# Wio_MB128_Test_rev_A.net
KiCad netlist of a schematic drawn in EAGLE
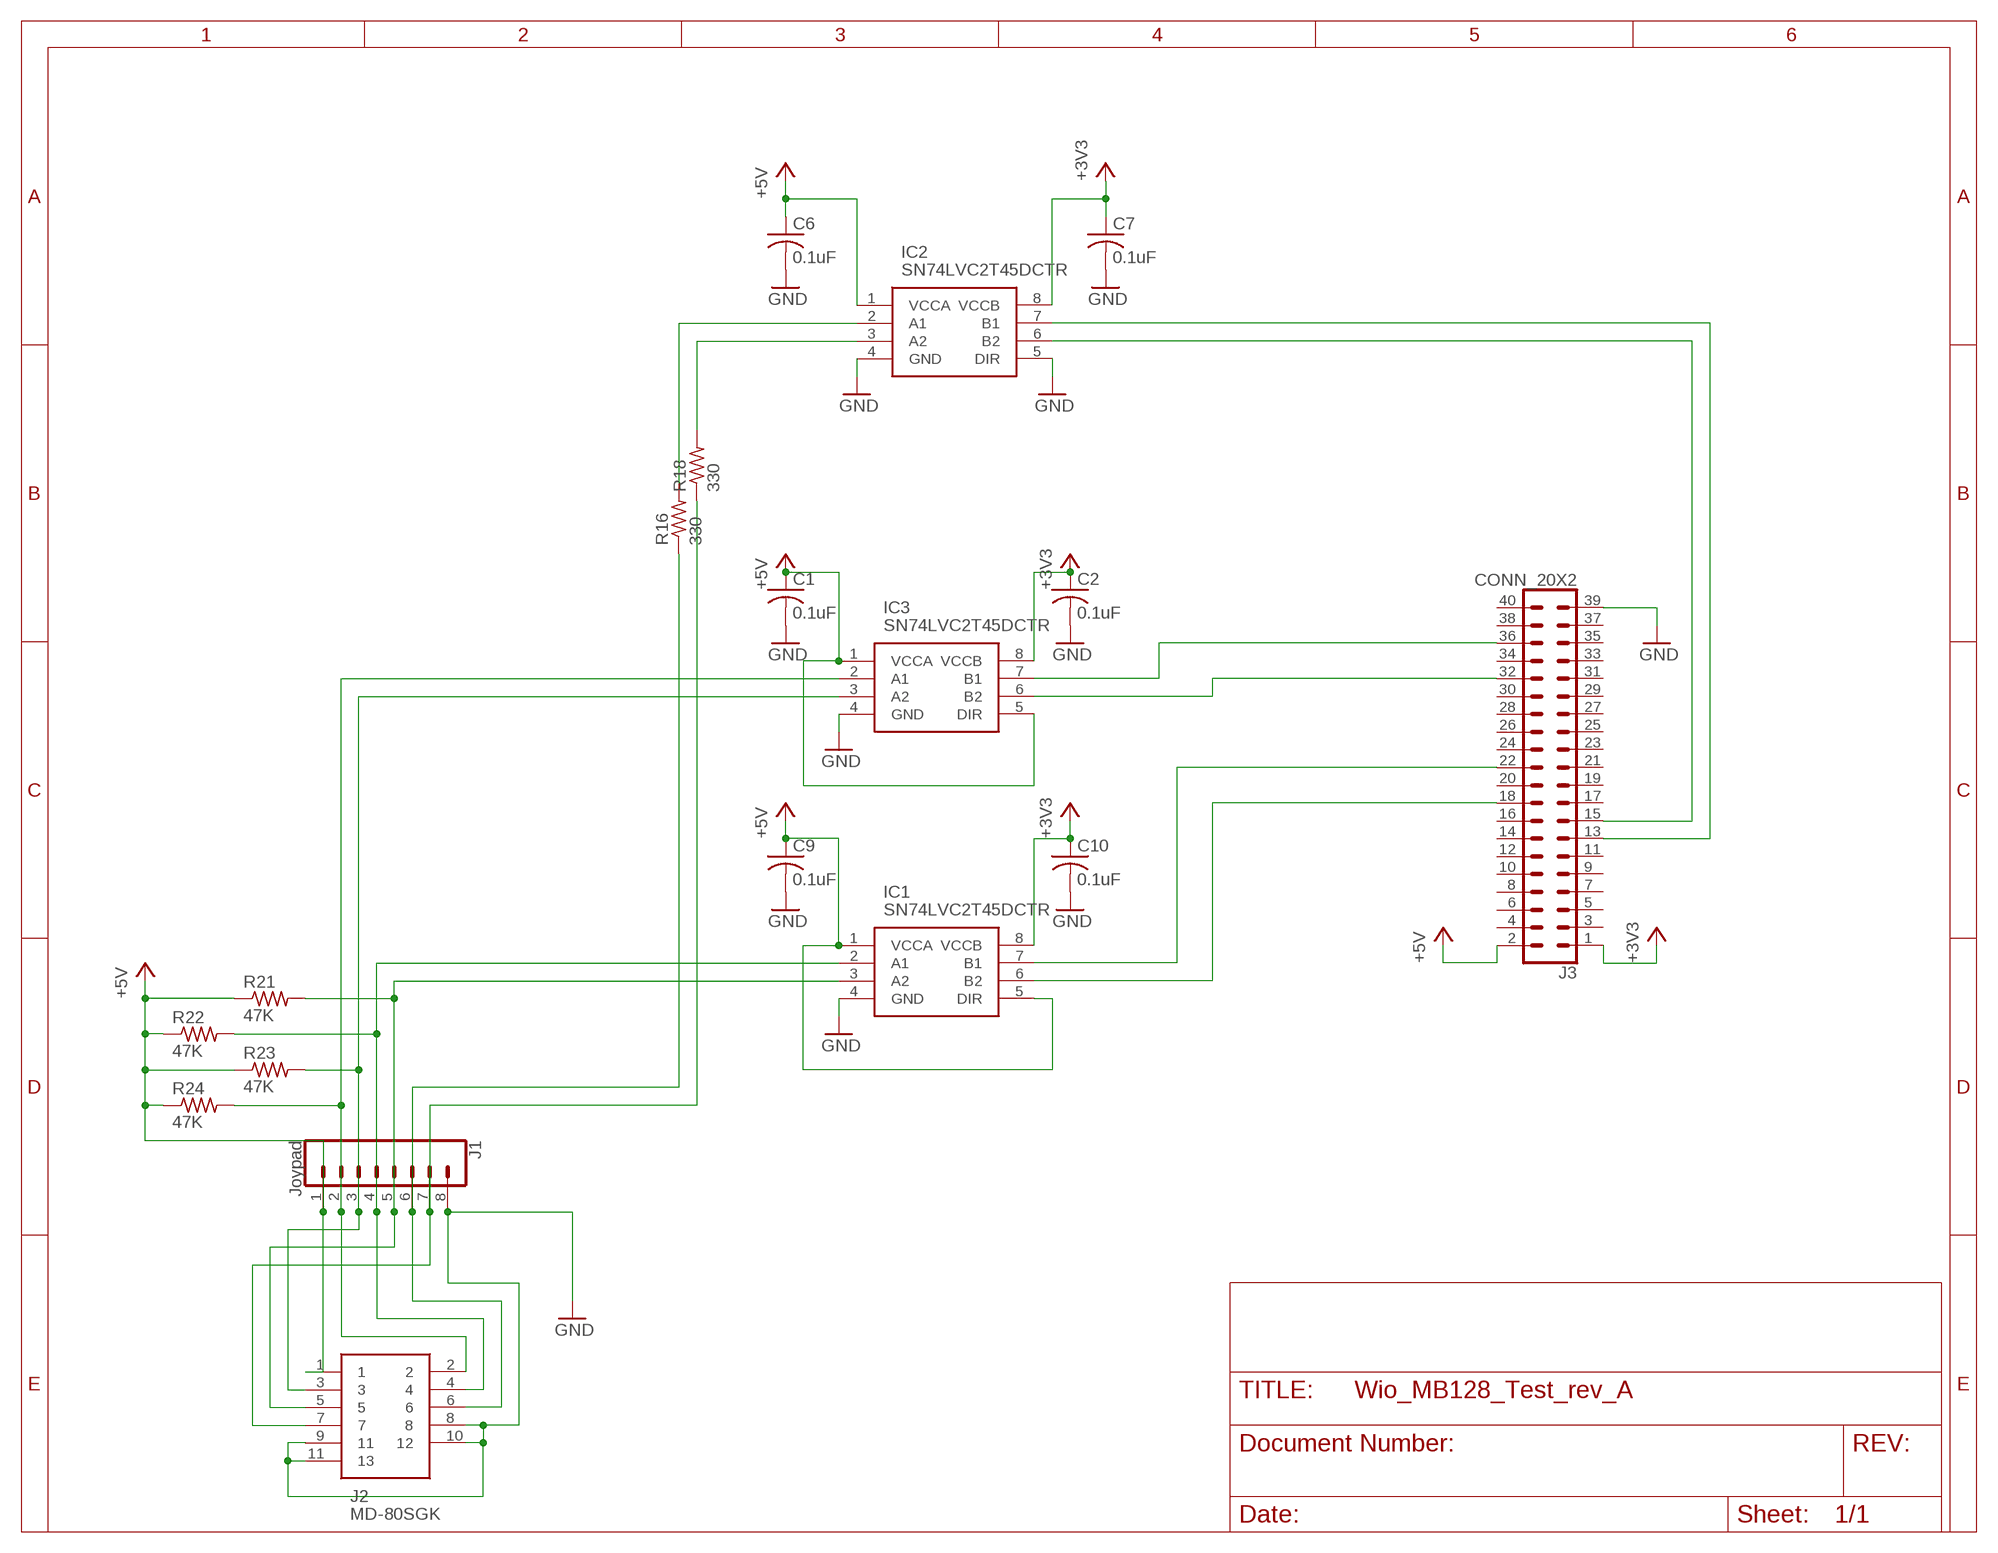
[diagram p0: schematic, sheet 1]

(export (version "E")
  (design (tool "Eeschema 10.0.6"))
  (components
    (comp (ref "C1")
      (value "0.1uF")
      (footprint "eagle-import:C0603")
      (libsource (lib "eagle-import") (part "C-USC0603"))
    )
    (comp (ref "C2")
      (value "0.1uF")
      (footprint "eagle-import:C0603")
      (libsource (lib "eagle-import") (part "C-USC0603"))
    )
    (comp (ref "C6")
      (value "0.1uF")
      (footprint "eagle-import:C0603")
      (libsource (lib "eagle-import") (part "C-USC0603"))
    )
    (comp (ref "C7")
      (value "0.1uF")
      (footprint "eagle-import:C0603")
      (libsource (lib "eagle-import") (part "C-USC0603"))
    )
    (comp (ref "C9")
      (value "0.1uF")
      (footprint "eagle-import:C0603")
      (libsource (lib "eagle-import") (part "C-USC0603"))
    )
    (comp (ref "C10")
      (value "0.1uF")
      (footprint "eagle-import:C0603")
      (libsource (lib "eagle-import") (part "C-USC0603"))
    )
    (comp (ref "IC1")
      (value "SN74LVC2T45DCTR")
      (footprint "eagle-import:SOP65P400X130-8N")
      (fields
        (field (name "MOUSER_PART_NUMBER") "595-SN74LVC2T45DCTR")
        (field (name "RS_PART_NUMBER") "9213022")
      )
      (libsource (lib "eagle-import") (part "SN74LVC2T45DCTR"))
    )
    (comp (ref "IC2")
      (value "SN74LVC2T45DCTR")
      (footprint "eagle-import:SOP65P400X130-8N")
      (fields
        (field (name "MOUSER_PART_NUMBER") "595-SN74LVC2T45DCTR")
        (field (name "RS_PART_NUMBER") "9213022")
      )
      (libsource (lib "eagle-import") (part "SN74LVC2T45DCTR"))
    )
    (comp (ref "IC3")
      (value "SN74LVC2T45DCTR")
      (footprint "eagle-import:SOP65P400X130-8N")
      (fields
        (field (name "MOUSER_PART_NUMBER") "595-SN74LVC2T45DCTR")
        (field (name "RS_PART_NUMBER") "9213022")
      )
      (libsource (lib "eagle-import") (part "SN74LVC2T45DCTR"))
    )
    (comp (ref "J1")
      (value "Joypad")
      (footprint "eagle-import:1X08")
      (libsource (lib "eagle-import") (part "CONN_08{dblquote}"))
    )
    (comp (ref "J2")
      (value "MD-80SGK")
      (footprint "eagle-import:MD80SGK")
      (fields (field (name "MOUSER_PART_NUMBER") "490-MD-80SGK"))
      (libsource (lib "eagle-import") (part "MD-80SGK"))
    )
    (comp (ref "J3")
      (value "CONN_20X2")
      (footprint "eagle-import:2X20")
      (libsource (lib "eagle-import") (part "CONN_20X2"))
    )
    (comp (ref "R16")
      (value "330")
      (footprint "eagle-import:R0603")
      (libsource (lib "eagle-import") (part "R-US_R0603"))
    )
    (comp (ref "R18")
      (value "330")
      (footprint "eagle-import:R0603")
      (libsource (lib "eagle-import") (part "R-US_R0603"))
    )
    (comp (ref "R21")
      (value "47K")
      (footprint "eagle-import:R0603")
      (libsource (lib "eagle-import") (part "R-US_R0603"))
    )
    (comp (ref "R22")
      (value "47K")
      (footprint "eagle-import:R0603")
      (libsource (lib "eagle-import") (part "R-US_R0603"))
    )
    (comp (ref "R23")
      (value "47K")
      (footprint "eagle-import:R0603")
      (libsource (lib "eagle-import") (part "R-US_R0603"))
    )
    (comp (ref "R24")
      (value "47K")
      (footprint "eagle-import:R0603")
      (libsource (lib "eagle-import") (part "R-US_R0603"))
    )
  )
  (nets
    (net (code "1") (name "+3V3") (class "Default")
      (node (ref "C10") (pin "1") (pinfunction "1_1") (pintype "passive"))
      (node (ref "C2") (pin "1") (pinfunction "1_1") (pintype "passive"))
      (node (ref "C7") (pin "1") (pinfunction "1_1") (pintype "passive"))
      (node (ref "IC1") (pin "8") (pinfunction "VCCB_8") (pintype "power_in"))
      (node (ref "IC2") (pin "8") (pinfunction "VCCB_8") (pintype "power_in"))
      (node (ref "IC3") (pin "8") (pinfunction "VCCB_8") (pintype "power_in"))
      (node (ref "J3") (pin "1") (pinfunction "1_1") (pintype "passive"))
    )
    (net (code "2") (name "+5V") (class "Default")
      (node (ref "C1") (pin "1") (pinfunction "1_1") (pintype "passive"))
      (node (ref "C6") (pin "1") (pinfunction "1_1") (pintype "passive"))
      (node (ref "C9") (pin "1") (pinfunction "1_1") (pintype "passive"))
      (node (ref "IC1") (pin "1") (pinfunction "VCCA_1") (pintype "power_in"))
      (node (ref "IC1") (pin "5") (pinfunction "DIR_5") (pintype "bidirectional"))
      (node (ref "IC2") (pin "1") (pinfunction "VCCA_1") (pintype "power_in"))
      (node (ref "IC3") (pin "1") (pinfunction "VCCA_1") (pintype "power_in"))
      (node (ref "IC3") (pin "5") (pinfunction "DIR_5") (pintype "bidirectional"))
      (node (ref "J1") (pin "1") (pinfunction "1_1") (pintype "passive"))
      (node (ref "J2") (pin "1") (pinfunction "1_1") (pintype "bidirectional"))
      (node (ref "J3") (pin "2") (pinfunction "2_2") (pintype "passive"))
      (node (ref "R21") (pin "1") (pinfunction "1_1") (pintype "passive"))
      (node (ref "R22") (pin "1") (pinfunction "1_1") (pintype "passive"))
      (node (ref "R23") (pin "1") (pinfunction "1_1") (pintype "passive"))
      (node (ref "R24") (pin "1") (pinfunction "1_1") (pintype "passive"))
    )
    (net (code "3") (name "GND") (class "Default")
      (node (ref "C1") (pin "2") (pinfunction "2_2") (pintype "passive"))
      (node (ref "C10") (pin "2") (pinfunction "2_2") (pintype "passive"))
      (node (ref "C2") (pin "2") (pinfunction "2_2") (pintype "passive"))
      (node (ref "C6") (pin "2") (pinfunction "2_2") (pintype "passive"))
      (node (ref "C7") (pin "2") (pinfunction "2_2") (pintype "passive"))
      (node (ref "C9") (pin "2") (pinfunction "2_2") (pintype "passive"))
      (node (ref "IC1") (pin "4") (pinfunction "GND_4") (pintype "power_in"))
      (node (ref "IC2") (pin "4") (pinfunction "GND_4") (pintype "power_in"))
      (node (ref "IC2") (pin "5") (pinfunction "DIR_5") (pintype "bidirectional"))
      (node (ref "IC3") (pin "4") (pinfunction "GND_4") (pintype "power_in"))
      (node (ref "J1") (pin "8") (pinfunction "8_8") (pintype "passive"))
      (node (ref "J2") (pin "10") (pinfunction "12_10") (pintype "bidirectional"))
      (node (ref "J2") (pin "11") (pinfunction "13_11") (pintype "bidirectional"))
      (node (ref "J2") (pin "8") (pinfunction "8_8") (pintype "bidirectional"))
      (node (ref "J2") (pin "9") (pinfunction "11_9") (pintype "bidirectional"))
      (node (ref "J3") (pin "39") (pinfunction "39_39") (pintype "passive"))
    )
    (net (code "4") (name "Net-(IC1-A1)") (class "Default")
      (node (ref "IC1") (pin "2") (pinfunction "A1_2") (pintype "bidirectional"))
      (node (ref "J1") (pin "4") (pinfunction "4_4") (pintype "passive"))
      (node (ref "J2") (pin "4") (pinfunction "4_4") (pintype "bidirectional"))
      (node (ref "R22") (pin "2") (pinfunction "2_2") (pintype "passive"))
    )
    (net (code "5") (name "Net-(IC1-A2)") (class "Default")
      (node (ref "IC1") (pin "3") (pinfunction "A2_3") (pintype "bidirectional"))
      (node (ref "J1") (pin "5") (pinfunction "5_5") (pintype "passive"))
      (node (ref "J2") (pin "5") (pinfunction "5_5") (pintype "bidirectional"))
      (node (ref "R21") (pin "2") (pinfunction "2_2") (pintype "passive"))
    )
    (net (code "6") (name "Net-(IC1-B1)") (class "Default")
      (node (ref "IC1") (pin "7") (pinfunction "B1_7") (pintype "bidirectional"))
      (node (ref "J3") (pin "22") (pinfunction "22_22") (pintype "passive"))
    )
    (net (code "7") (name "Net-(IC1-B2)") (class "Default")
      (node (ref "IC1") (pin "6") (pinfunction "B2_6") (pintype "bidirectional"))
      (node (ref "J3") (pin "18") (pinfunction "18_18") (pintype "passive"))
    )
    (net (code "8") (name "Net-(IC2-A1)") (class "Default")
      (node (ref "IC2") (pin "2") (pinfunction "A1_2") (pintype "bidirectional"))
      (node (ref "R16") (pin "2") (pinfunction "2_2") (pintype "passive"))
    )
    (net (code "9") (name "Net-(IC2-A2)") (class "Default")
      (node (ref "IC2") (pin "3") (pinfunction "A2_3") (pintype "bidirectional"))
      (node (ref "R18") (pin "2") (pinfunction "2_2") (pintype "passive"))
    )
    (net (code "10") (name "Net-(IC2-B1)") (class "Default")
      (node (ref "IC2") (pin "7") (pinfunction "B1_7") (pintype "bidirectional"))
      (node (ref "J3") (pin "13") (pinfunction "13_13") (pintype "passive"))
    )
    (net (code "11") (name "Net-(IC2-B2)") (class "Default")
      (node (ref "IC2") (pin "6") (pinfunction "B2_6") (pintype "bidirectional"))
      (node (ref "J3") (pin "15") (pinfunction "15_15") (pintype "passive"))
    )
    (net (code "12") (name "Net-(IC3-A1)") (class "Default")
      (node (ref "IC3") (pin "2") (pinfunction "A1_2") (pintype "bidirectional"))
      (node (ref "J1") (pin "2") (pinfunction "2_2") (pintype "passive"))
      (node (ref "J2") (pin "2") (pinfunction "2_2") (pintype "bidirectional"))
      (node (ref "R24") (pin "2") (pinfunction "2_2") (pintype "passive"))
    )
    (net (code "13") (name "Net-(IC3-A2)") (class "Default")
      (node (ref "IC3") (pin "3") (pinfunction "A2_3") (pintype "bidirectional"))
      (node (ref "J1") (pin "3") (pinfunction "3_3") (pintype "passive"))
      (node (ref "J2") (pin "3") (pinfunction "3_3") (pintype "bidirectional"))
      (node (ref "R23") (pin "2") (pinfunction "2_2") (pintype "passive"))
    )
    (net (code "14") (name "Net-(IC3-B1)") (class "Default")
      (node (ref "IC3") (pin "7") (pinfunction "B1_7") (pintype "bidirectional"))
      (node (ref "J3") (pin "36") (pinfunction "36_36") (pintype "passive"))
    )
    (net (code "15") (name "Net-(IC3-B2)") (class "Default")
      (node (ref "IC3") (pin "6") (pinfunction "B2_6") (pintype "bidirectional"))
      (node (ref "J3") (pin "32") (pinfunction "32_32") (pintype "passive"))
    )
    (net (code "16") (name "Net-(J1-Pad6)") (class "Default")
      (node (ref "J1") (pin "6") (pinfunction "6_6") (pintype "passive"))
      (node (ref "J2") (pin "6") (pinfunction "6_6") (pintype "bidirectional"))
      (node (ref "R16") (pin "1") (pinfunction "1_1") (pintype "passive"))
    )
    (net (code "17") (name "Net-(J1-Pad7)") (class "Default")
      (node (ref "J1") (pin "7") (pinfunction "7_7") (pintype "passive"))
      (node (ref "J2") (pin "7") (pinfunction "7_7") (pintype "bidirectional"))
      (node (ref "R18") (pin "1") (pinfunction "1_1") (pintype "passive"))
    )
    (net (code "18") (name "unconnected-(J3-Pad3)") (class "Default")
      (node (ref "J3") (pin "3") (pinfunction "3_3") (pintype "passive"))
    )
    (net (code "19") (name "unconnected-(J3-Pad4)") (class "Default")
      (node (ref "J3") (pin "4") (pinfunction "4_4") (pintype "passive"))
    )
    (net (code "20") (name "unconnected-(J3-Pad5)") (class "Default")
      (node (ref "J3") (pin "5") (pinfunction "5_5") (pintype "passive"))
    )
    (net (code "21") (name "unconnected-(J3-Pad6)") (class "Default")
      (node (ref "J3") (pin "6") (pinfunction "6_6") (pintype "passive"))
    )
    (net (code "22") (name "unconnected-(J3-Pad7)") (class "Default")
      (node (ref "J3") (pin "7") (pinfunction "7_7") (pintype "passive"))
    )
    (net (code "23") (name "unconnected-(J3-Pad8)") (class "Default")
      (node (ref "J3") (pin "8") (pinfunction "8_8") (pintype "passive"))
    )
    (net (code "24") (name "unconnected-(J3-Pad9)") (class "Default")
      (node (ref "J3") (pin "9") (pinfunction "9_9") (pintype "passive"))
    )
    (net (code "25") (name "unconnected-(J3-Pad10)") (class "Default")
      (node (ref "J3") (pin "10") (pinfunction "10_10") (pintype "passive"))
    )
    (net (code "26") (name "unconnected-(J3-Pad11)") (class "Default")
      (node (ref "J3") (pin "11") (pinfunction "11_11") (pintype "passive"))
    )
    (net (code "27") (name "unconnected-(J3-Pad12)") (class "Default")
      (node (ref "J3") (pin "12") (pinfunction "12_12") (pintype "passive"))
    )
    (net (code "28") (name "unconnected-(J3-Pad14)") (class "Default")
      (node (ref "J3") (pin "14") (pinfunction "14_14") (pintype "passive"))
    )
    (net (code "29") (name "unconnected-(J3-Pad16)") (class "Default")
      (node (ref "J3") (pin "16") (pinfunction "16_16") (pintype "passive"))
    )
    (net (code "30") (name "unconnected-(J3-Pad17)") (class "Default")
      (node (ref "J3") (pin "17") (pinfunction "17_17") (pintype "passive"))
    )
    (net (code "31") (name "unconnected-(J3-Pad19)") (class "Default")
      (node (ref "J3") (pin "19") (pinfunction "19_19") (pintype "passive"))
    )
    (net (code "32") (name "unconnected-(J3-Pad20)") (class "Default")
      (node (ref "J3") (pin "20") (pinfunction "20_20") (pintype "passive"))
    )
    (net (code "33") (name "unconnected-(J3-Pad21)") (class "Default")
      (node (ref "J3") (pin "21") (pinfunction "21_21") (pintype "passive"))
    )
    (net (code "34") (name "unconnected-(J3-Pad23)") (class "Default")
      (node (ref "J3") (pin "23") (pinfunction "23_23") (pintype "passive"))
    )
    (net (code "35") (name "unconnected-(J3-Pad24)") (class "Default")
      (node (ref "J3") (pin "24") (pinfunction "24_24") (pintype "passive"))
    )
    (net (code "36") (name "unconnected-(J3-Pad25)") (class "Default")
      (node (ref "J3") (pin "25") (pinfunction "25_25") (pintype "passive"))
    )
    (net (code "37") (name "unconnected-(J3-Pad26)") (class "Default")
      (node (ref "J3") (pin "26") (pinfunction "26_26") (pintype "passive"))
    )
    (net (code "38") (name "unconnected-(J3-Pad27)") (class "Default")
      (node (ref "J3") (pin "27") (pinfunction "27_27") (pintype "passive"))
    )
    (net (code "39") (name "unconnected-(J3-Pad28)") (class "Default")
      (node (ref "J3") (pin "28") (pinfunction "28_28") (pintype "passive"))
    )
    (net (code "40") (name "unconnected-(J3-Pad29)") (class "Default")
      (node (ref "J3") (pin "29") (pinfunction "29_29") (pintype "passive"))
    )
    (net (code "41") (name "unconnected-(J3-Pad30)") (class "Default")
      (node (ref "J3") (pin "30") (pinfunction "30_30") (pintype "passive"))
    )
    (net (code "42") (name "unconnected-(J3-Pad31)") (class "Default")
      (node (ref "J3") (pin "31") (pinfunction "31_31") (pintype "passive"))
    )
    (net (code "43") (name "unconnected-(J3-Pad33)") (class "Default")
      (node (ref "J3") (pin "33") (pinfunction "33_33") (pintype "passive"))
    )
    (net (code "44") (name "unconnected-(J3-Pad34)") (class "Default")
      (node (ref "J3") (pin "34") (pinfunction "34_34") (pintype "passive"))
    )
    (net (code "45") (name "unconnected-(J3-Pad35)") (class "Default")
      (node (ref "J3") (pin "35") (pinfunction "35_35") (pintype "passive"))
    )
    (net (code "46") (name "unconnected-(J3-Pad37)") (class "Default")
      (node (ref "J3") (pin "37") (pinfunction "37_37") (pintype "passive"))
    )
    (net (code "47") (name "unconnected-(J3-Pad38)") (class "Default")
      (node (ref "J3") (pin "38") (pinfunction "38_38") (pintype "passive"))
    )
    (net (code "48") (name "unconnected-(J3-Pad40)") (class "Default")
      (node (ref "J3") (pin "40") (pinfunction "40_40") (pintype "passive"))
    )
  )
)
